# PowerSupplies.net
KiCad netlist of a schematic drawn in Altium Designer
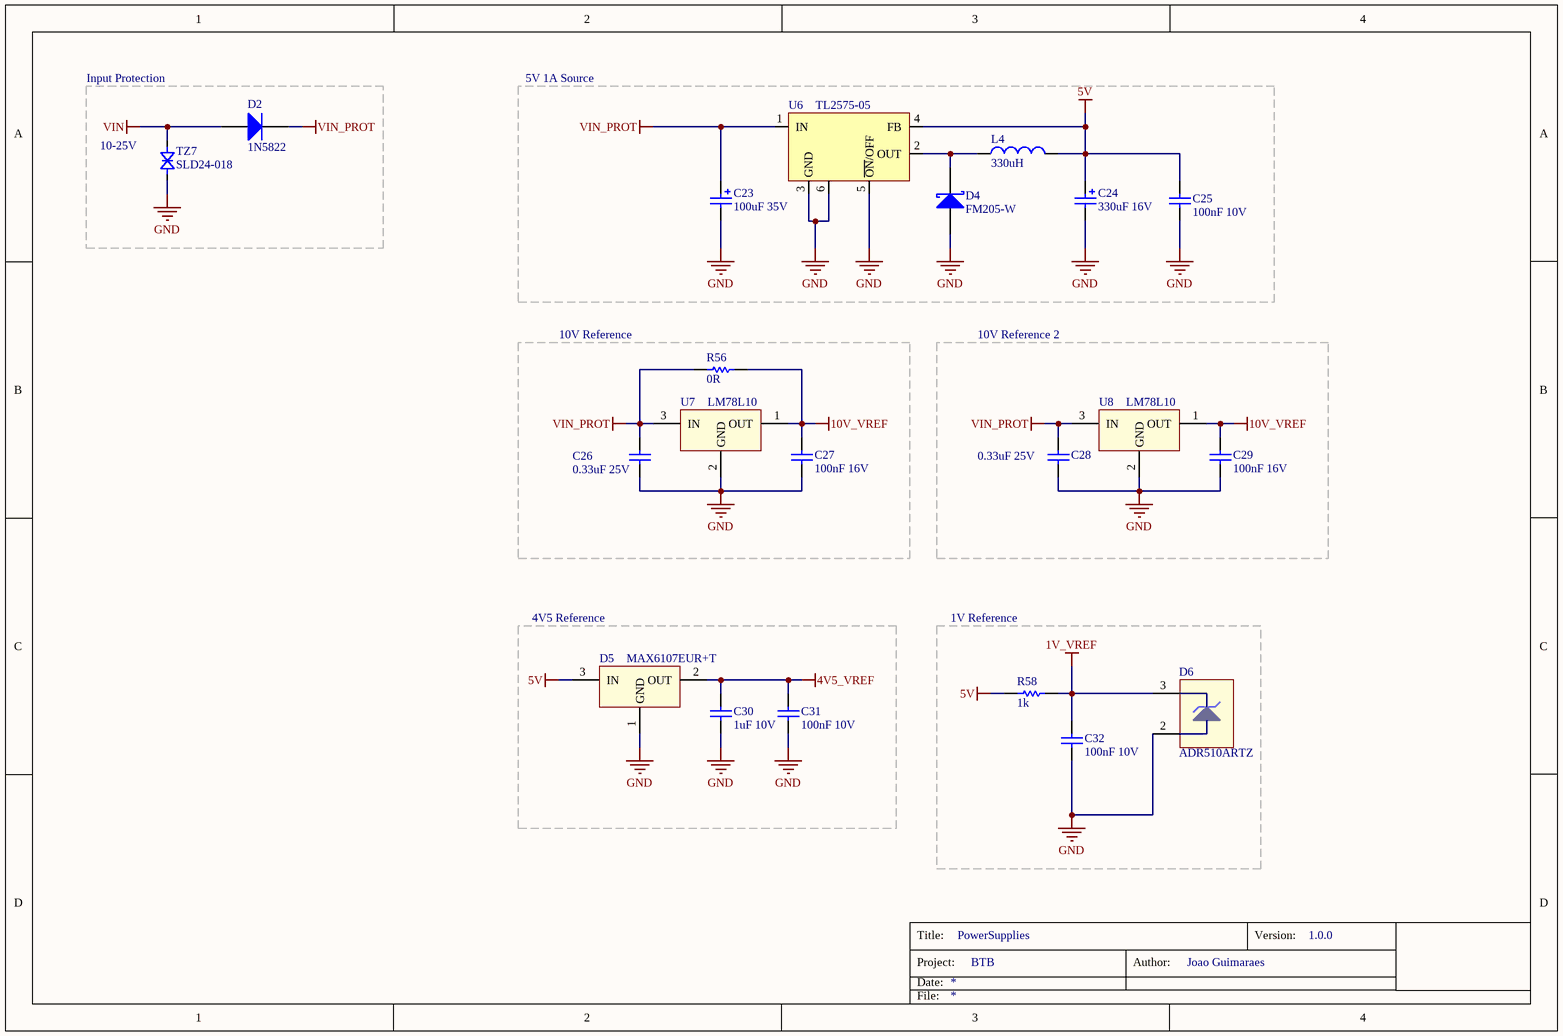
[diagram p0: PowerSupplies.SchDoc]

(export (version "E")
  (design (tool "Eeschema 10.0.6"))
  (components
    (comp (ref "C23")
      (value "100uF 35V")
      (footprint "WCAP-ASLI_6.3x7.7")
      (description "Polarized Capacitor (Surface Mount)")
      (fields
        (field (name "PARTNUMBER") "CAP.100u.35V.20%.SMD.6,3x7,7")
        (field (name "MANUFACTURER") "Wurth")
      )
      (libsource (lib "IntLib") (part "Cap Pol"))
    )
    (comp (ref "C24")
      (value "330uF 16V")
      (footprint "WCAP-ASLI_6.3x5.5")
      (description "Polarized Capacitor (Surface Mount)")
      (fields
        (field (name "PARTNUMBER") "CAP.330u.6V3.20%.SMD.6,3x5,4")
        (field (name "MANUFACTURER") "Wurth")
      )
      (libsource (lib "IntLib") (part "Cap Pol"))
    )
    (comp (ref "C25")
      (value "100nF 10V")
      (footprint "C0805")
      (description "Capacitor")
      (fields (field (name "PARTNUMBER") "CAP.100n.10V.20%.SMD.0402") (field (name "MANUFACTURER") "Wurth"))
      (libsource (lib "IntLib") (part "Cap"))
    )
    (comp (ref "C26")
      (value "0.33uF 25V")
      (footprint "C0805")
      (description "Capacitor")
      (fields (field (name "PARTNUMBER") "CAP.0.33u.25V.10%.SMD.0805") (field (name "MANUFACTURER") "Vishay"))
      (libsource (lib "IntLib") (part "Cap"))
    )
    (comp (ref "C27")
      (value "100nF 16V")
      (footprint "C0805")
      (description "Capacitor")
      (fields (field (name "PARTNUMBER") "CAP.100n.16V.10%.SMD.0402") (field (name "MANUFACTURER") "Wurth"))
      (libsource (lib "IntLib") (part "Cap"))
    )
    (comp (ref "C28")
      (value "0.33uF 25V")
      (footprint "C0805")
      (description "Capacitor")
      (fields (field (name "PARTNUMBER") "CAP.0.33u.25V.10%.SMD.0805") (field (name "MANUFACTURER") "Vishay"))
      (libsource (lib "IntLib") (part "Cap"))
    )
    (comp (ref "C29")
      (value "100nF 16V")
      (footprint "C0805")
      (description "Capacitor")
      (fields (field (name "PARTNUMBER") "CAP.100n.16V.10%.SMD.0805") (field (name "MANUFACTURER") "Wurth"))
      (libsource (lib "IntLib") (part "Cap"))
    )
    (comp (ref "C30")
      (value "1uF 10V")
      (footprint "C0805")
      (description "Capacitor")
      (fields (field (name "PARTNUMBER") "CAP.1u.10V.10%.SMD.0805") (field (name "MANUFACTURER") "Vishay"))
      (libsource (lib "IntLib") (part "Cap"))
    )
    (comp (ref "C31")
      (value "100nF 10V")
      (footprint "C0805")
      (description "Capacitor")
      (fields (field (name "PARTNUMBER") "CAP.1u.10V.10%.SMD.0805") (field (name "MANUFACTURER") "Vishay"))
      (libsource (lib "IntLib") (part "Cap"))
    )
    (comp (ref "C32")
      (value "100nF 10V")
      (footprint "C0805")
      (description "Capacitor")
      (fields (field (name "PARTNUMBER") "CAP.1u.10V.10%.SMD.0805") (field (name "MANUFACTURER") "Vishay"))
      (libsource (lib "IntLib") (part "Cap"))
    )
    (comp (ref "D2")
      (value "1N5822")
      (footprint "PIN-W2/E2.8")
      (description "Default Diode")
      (fields (field (name "MANUFACTURER") "STMicroelectronics"))
      (libsource (lib "IntLib") (part "Diode"))
    )
    (comp (ref "D4")
      (value "FM205-W")
      (footprint "DO-214AC")
      (description "Schottky Diodes & Rectifiers Vr/40V Io/2A T/R")
      (fields (field (name "MANUFACTURER") "Rectron"))
      (libsource (lib "IntLib") (part "FM5819-W"))
    )
    (comp (ref "D5")
      (value "MAX6107EUR+T")
      (footprint "SOT23_M")
      (description "4V5 Voltage References uPower Low-Dropout Voltage Ref")
      (fields (field (name "PARTNUMBER") "MAX6107EUR") (field (name "MANUFACTURER") "Maxim Integrated"))
      (libsource (lib "IntLib") (part "MAX6107EUR+T"))
    )
    (comp (ref "D6")
      (value "ADR510ARTZ")
      (footprint "SOT23_M")
      (description "Voltage References 1.0V Prec Shunt Low Noise")
      (fields (field (name "MANUFACTURER") "Analog Devices"))
      (libsource (lib "IntLib") (part "ADR510ARTZ-REEL7"))
    )
    (comp (ref "L4")
      (value "330uH")
      (footprint "SDE0805A")
      (description "Chip Inductor")
      (fields (field (name "PARTNUMBER") "SDE0805A-331K") (field (name "MANUFACTURER") "Bourns"))
      (libsource (lib "IntLib") (part "Inductor"))
    )
    (comp (ref "R56")
      (value "0R")
      (footprint "6-0805_M")
      (description "Resistor")
      (fields (field (name "PARTNUMBER") "RES.0R.1/8W.5%.SMD.0805") (field (name "MANUFACTURER") "Vishay"))
      (libsource (lib "IntLib") (part "Res"))
    )
    (comp (ref "R58")
      (value "1k")
      (footprint "6-0805_M")
      (description "Resistor")
      (fields (field (name "PARTNUMBER") "RES.1K.1/8W.5%.SMD.0805") (field (name "MANUFACTURER") "Yageo"))
      (libsource (lib "IntLib") (part "Res"))
    )
    (comp (ref "TZ7")
      (value "SLD24-018")
      (footprint "P600")
      (description "TVS Bi-Directional VR=30V")
      (fields (field (name "MANUFACTURER") "Littelfuse"))
      (libsource (lib "IntLib") (part "SLD30-018"))
    )
    (comp (ref "U6")
      (value "TL2575-05")
      (footprint "TO-263-5")
      (description "Switching Voltage Regulators 1-A Step-Down Voltage")
      (fields (field (name "MANUFACTURER") "Texas Instruments"))
      (libsource (lib "IntLib") (part "TL2575-05IKTTR"))
    )
    (comp (ref "U7")
      (value "LM78L10")
      (footprint "TO-92A")
      (description "3-TERMINAL 0.1A POSITIVE VOLTAGE REGULATOR")
      (fields (field (name "MANUFACTURER") "ON Semiconductor"))
      (libsource (lib "IntLib") (part "LM78L10"))
    )
    (comp (ref "U8")
      (value "LM78L10")
      (footprint "TO-92A")
      (description "3-TERMINAL 0.1A POSITIVE VOLTAGE REGULATOR")
      (libsource (lib "IntLib") (part "LM78L10"))
    )
  )
  (nets
    (net (code "1") (name "1V_VREF") (class "Default")
      (node (ref "C32") (pin "1") (pinfunction "1_1") (pintype "passive"))
      (node (ref "D6") (pin "3") (pinfunction "K_3") (pintype "passive"))
      (node (ref "R58") (pin "2") (pinfunction "2_2") (pintype "passive"))
    )
    (net (code "2") (name "4V5_VREF") (class "Default")
      (node (ref "C30") (pin "1") (pinfunction "1_1") (pintype "passive"))
      (node (ref "C31") (pin "1") (pinfunction "1_1") (pintype "passive"))
      (node (ref "D5") (pin "2") (pinfunction "OUT_2") (pintype "passive"))
    )
    (net (code "3") (name "5V") (class "Default")
      (node (ref "C24") (pin "1") (pinfunction "1_1") (pintype "passive"))
      (node (ref "C25") (pin "1") (pinfunction "1_1") (pintype "passive"))
      (node (ref "D5") (pin "3") (pinfunction "IN_3") (pintype "power_in"))
      (node (ref "L4") (pin "2") (pinfunction "2_2") (pintype "passive"))
      (node (ref "R58") (pin "1") (pinfunction "1_1") (pintype "passive"))
      (node (ref "U6") (pin "4") (pinfunction "FB_4") (pintype "passive"))
    )
    (net (code "4") (name "10V_VREF") (class "Default")
      (node (ref "C27") (pin "1") (pinfunction "1_1") (pintype "passive"))
      (node (ref "C29") (pin "1") (pinfunction "1_1") (pintype "passive"))
      (node (ref "R56") (pin "2") (pinfunction "2_2") (pintype "passive"))
      (node (ref "U7") (pin "1") (pinfunction "OUT_1") (pintype "passive"))
      (node (ref "U8") (pin "1") (pinfunction "OUT_1") (pintype "passive"))
    )
    (net (code "5") (name "GND") (class "Default")
      (node (ref "C23") (pin "2") (pinfunction "2_2") (pintype "passive"))
      (node (ref "C24") (pin "2") (pinfunction "2_2") (pintype "passive"))
      (node (ref "C25") (pin "2") (pinfunction "2_2") (pintype "passive"))
      (node (ref "C26") (pin "2") (pinfunction "2_2") (pintype "passive"))
      (node (ref "C27") (pin "2") (pinfunction "2_2") (pintype "passive"))
      (node (ref "C28") (pin "2") (pinfunction "2_2") (pintype "passive"))
      (node (ref "C29") (pin "2") (pinfunction "2_2") (pintype "passive"))
      (node (ref "C30") (pin "2") (pinfunction "2_2") (pintype "passive"))
      (node (ref "C31") (pin "2") (pinfunction "2_2") (pintype "passive"))
      (node (ref "C32") (pin "2") (pinfunction "2_2") (pintype "passive"))
      (node (ref "D4") (pin "1") (pinfunction "A_1") (pintype "passive"))
      (node (ref "D5") (pin "1") (pinfunction "GND_1") (pintype "power_in"))
      (node (ref "D6") (pin "2") (pinfunction "A_2") (pintype "passive"))
      (node (ref "TZ7") (pin "1") (pinfunction "A_1") (pintype "passive"))
      (node (ref "U6") (pin "3") (pinfunction "GND_3") (pintype "power_in"))
      (node (ref "U6") (pin "5") (pinfunction "~{ON}/OFF_5") (pintype "power_in"))
      (node (ref "U6") (pin "6") (pinfunction "GND_6") (pintype "power_in"))
      (node (ref "U7") (pin "2") (pinfunction "GND_2") (pintype "power_in"))
      (node (ref "U8") (pin "2") (pinfunction "GND_2") (pintype "power_in"))
    )
    (net (code "6") (name "Net-(D4-K)") (class "Default")
      (node (ref "D4") (pin "2") (pinfunction "K_2") (pintype "passive"))
      (node (ref "L4") (pin "1") (pinfunction "1_1") (pintype "passive"))
      (node (ref "U6") (pin "2") (pinfunction "OUT_2") (pintype "power_in"))
    )
    (net (code "7") (name "VIN") (class "Default")
      (node (ref "D2") (pin "1") (pinfunction "A_1") (pintype "passive"))
      (node (ref "TZ7") (pin "2") (pinfunction "K_2") (pintype "passive"))
    )
    (net (code "8") (name "VIN_PROT") (class "Default")
      (node (ref "C23") (pin "1") (pinfunction "1_1") (pintype "passive"))
      (node (ref "C26") (pin "1") (pinfunction "1_1") (pintype "passive"))
      (node (ref "C28") (pin "1") (pinfunction "1_1") (pintype "passive"))
      (node (ref "D2") (pin "2") (pinfunction "K_2") (pintype "passive"))
      (node (ref "R56") (pin "1") (pinfunction "1_1") (pintype "passive"))
      (node (ref "U6") (pin "1") (pinfunction "IN_1") (pintype "power_in"))
      (node (ref "U7") (pin "3") (pinfunction "IN_3") (pintype "power_in"))
      (node (ref "U8") (pin "3") (pinfunction "IN_3") (pintype "power_in"))
    )
  )
)
